# fpv2.net
KiCad netlist of a schematic drawn in EAGLE
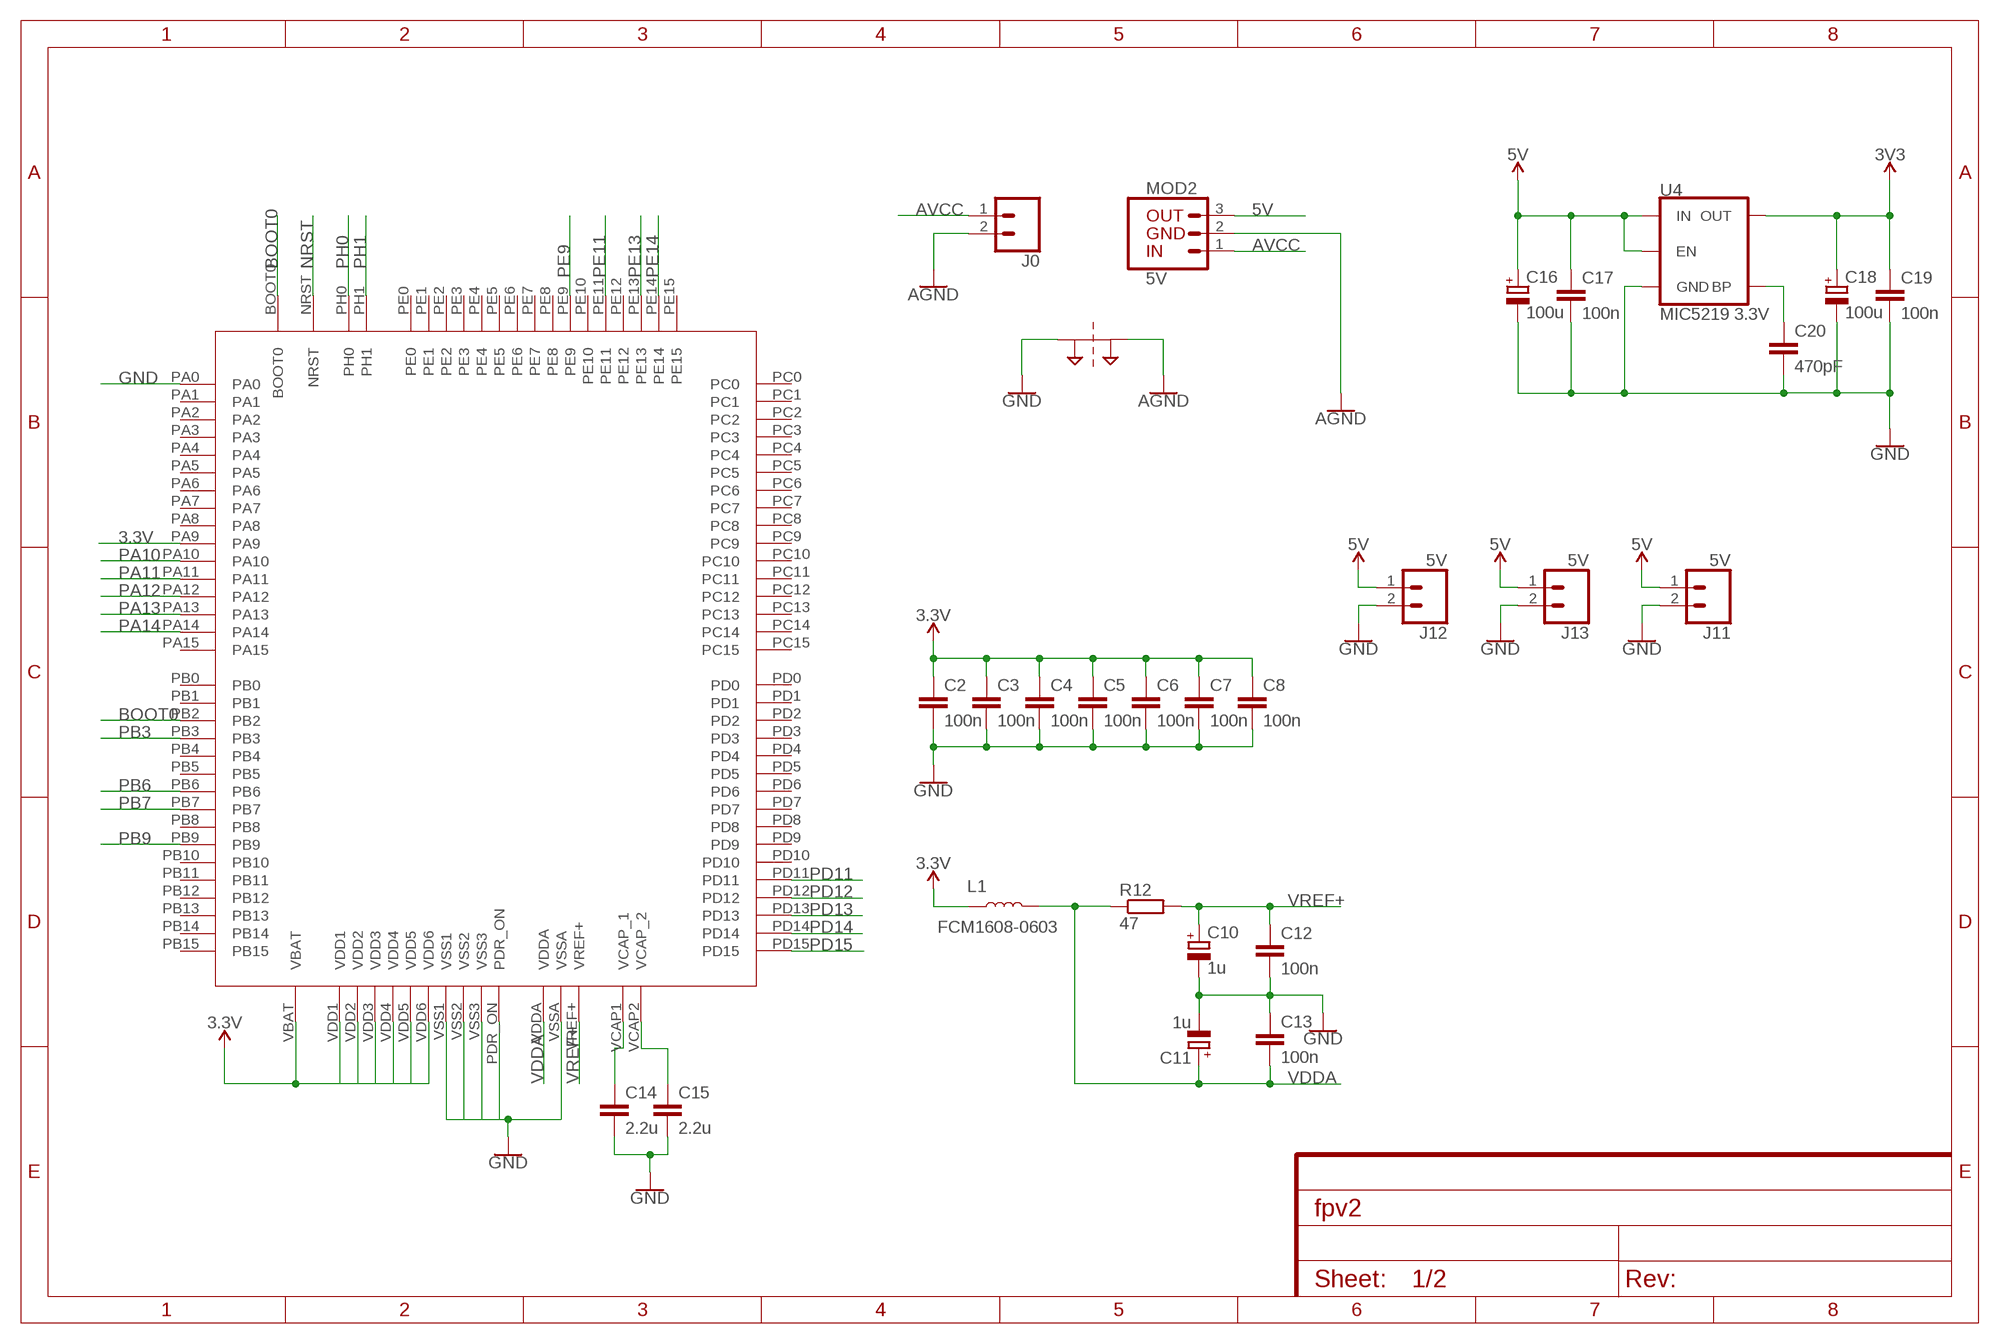
[diagram p0: schematic, sheet 1]
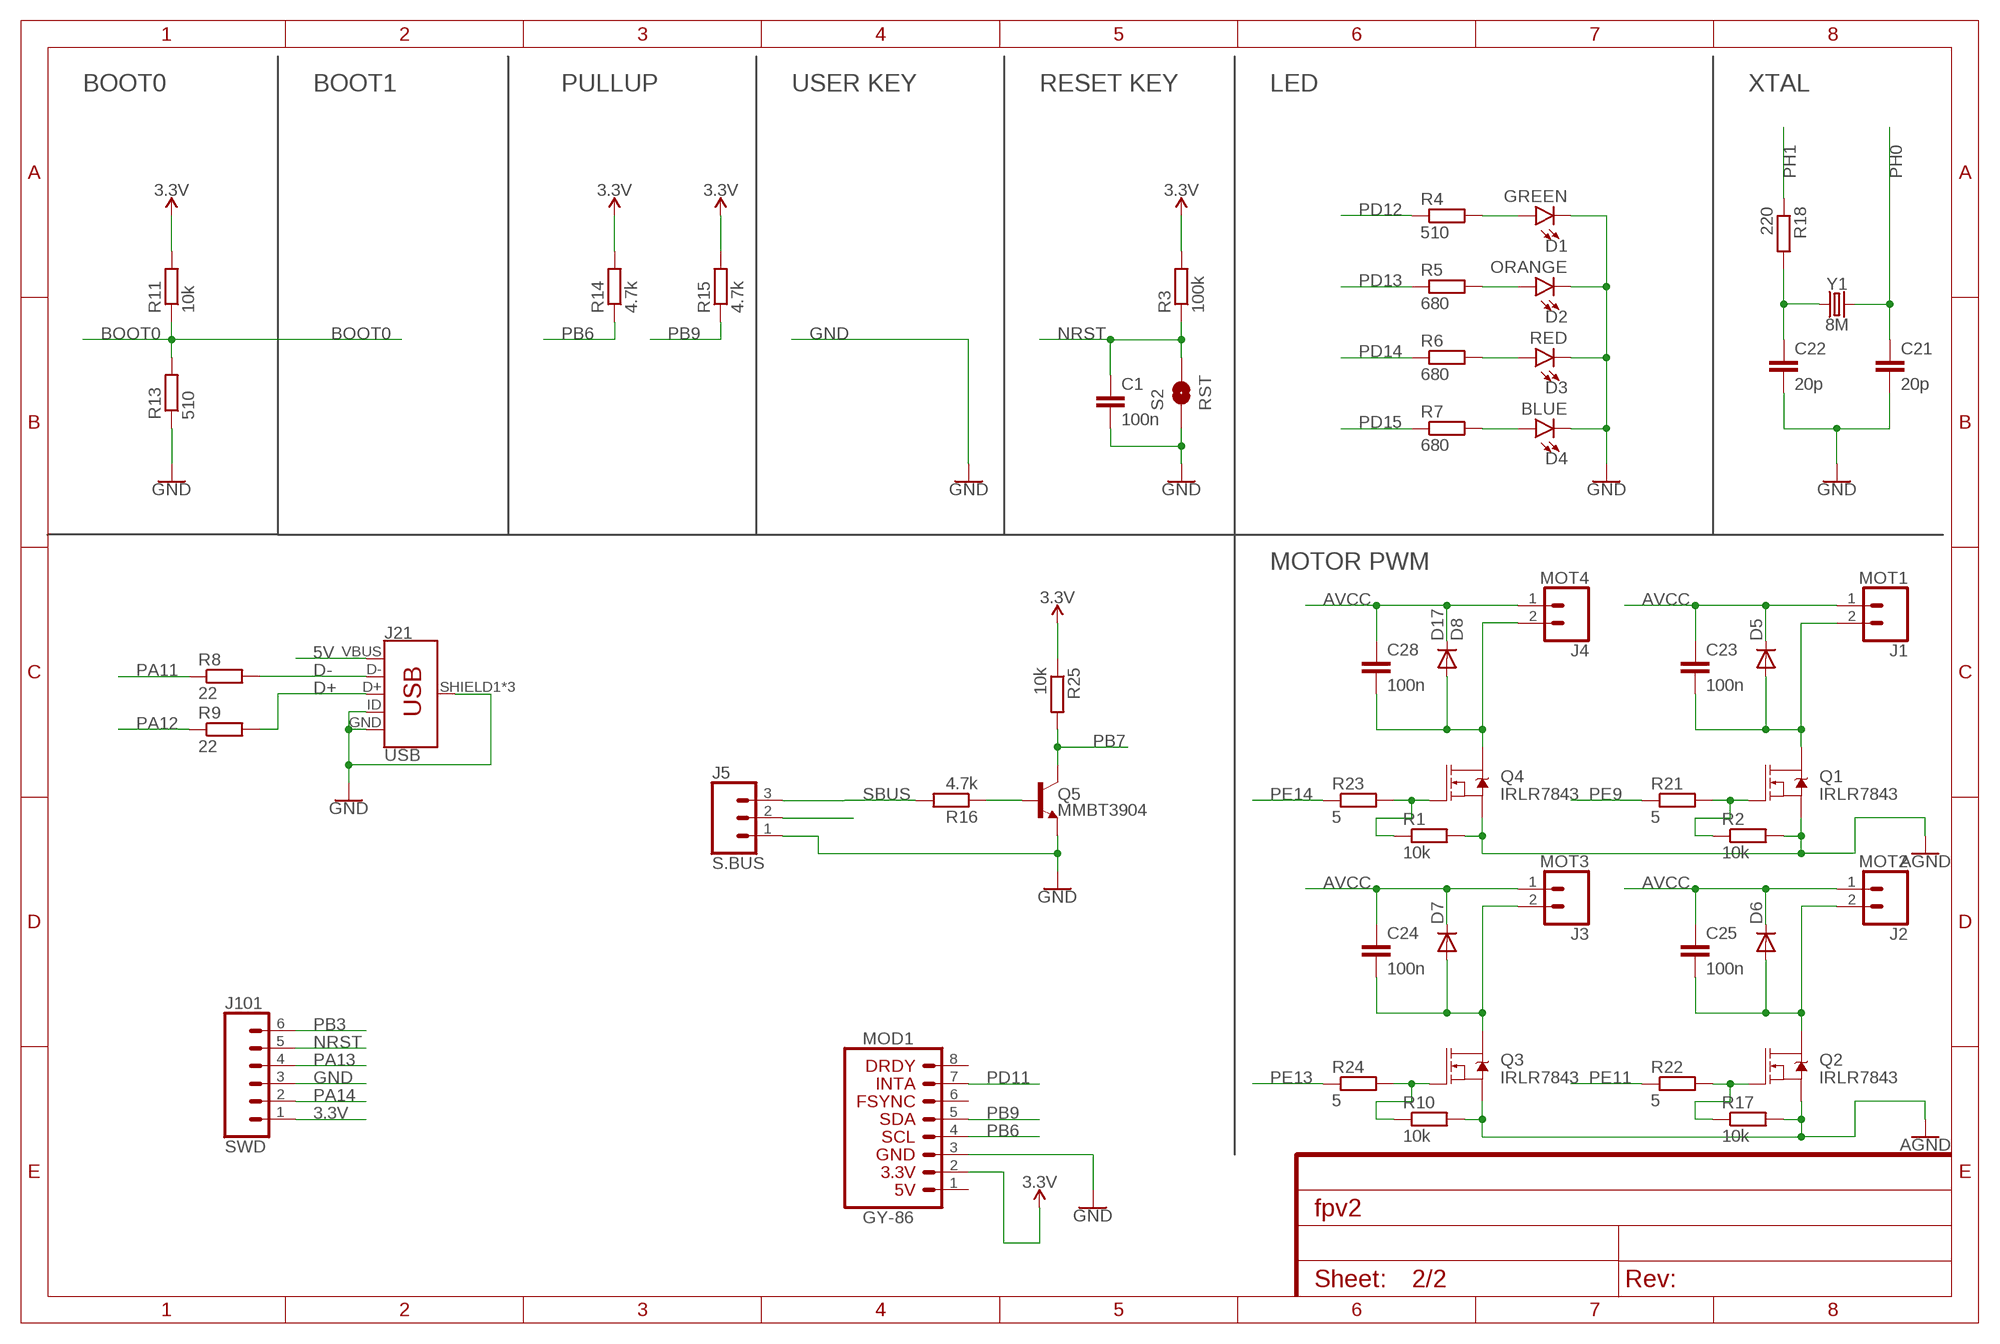
[diagram p1: schematic, sheet 2]

(export (version "E")
  (design (tool "Eeschema 10.0.6"))
  (components
    (comp (ref "C2")
      (value "100n")
      (footprint "eagle-import:C0603")
      (libsource (lib "eagle-import") (part "C-EUC0603"))
    )
    (comp (ref "C3")
      (value "100n")
      (footprint "eagle-import:C0603")
      (libsource (lib "eagle-import") (part "C-EUC0603"))
    )
    (comp (ref "C4")
      (value "100n")
      (footprint "eagle-import:C0603")
      (libsource (lib "eagle-import") (part "C-EUC0603"))
    )
    (comp (ref "C5")
      (value "100n")
      (footprint "eagle-import:C0603")
      (libsource (lib "eagle-import") (part "C-EUC0603"))
    )
    (comp (ref "C6")
      (value "100n")
      (footprint "eagle-import:C0603")
      (libsource (lib "eagle-import") (part "C-EUC0603"))
    )
    (comp (ref "C7")
      (value "100n")
      (footprint "eagle-import:C0603")
      (libsource (lib "eagle-import") (part "C-EUC0603"))
    )
    (comp (ref "C8")
      (value "100n")
      (footprint "eagle-import:C0603")
      (libsource (lib "eagle-import") (part "C-EUC0603"))
    )
    (comp (ref "C10")
      (value "1u")
      (footprint "eagle-import:A_3216-18R")
      (libsource (lib "eagle-import") (part "CPOL-EUA/3216-18R"))
    )
    (comp (ref "C11")
      (value "1u")
      (footprint "eagle-import:A_3216-18R")
      (libsource (lib "eagle-import") (part "CPOL-EUA/3216-18R"))
    )
    (comp (ref "C12")
      (value "100n")
      (footprint "eagle-import:C0603")
      (libsource (lib "eagle-import") (part "C-EUC0603"))
    )
    (comp (ref "C13")
      (value "100n")
      (footprint "eagle-import:C0603")
      (libsource (lib "eagle-import") (part "C-EUC0603"))
    )
    (comp (ref "C14")
      (value "2.2u")
      (footprint "eagle-import:C1206")
      (libsource (lib "eagle-import") (part "C-EUC1206"))
    )
    (comp (ref "C15")
      (value "2.2u")
      (footprint "eagle-import:C1206")
      (libsource (lib "eagle-import") (part "C-EUC1206"))
    )
    (comp (ref "C16")
      (value "100u")
      (footprint "eagle-import:SMC_B")
      (libsource (lib "eagle-import") (part "CPOL-EUSMCB"))
    )
    (comp (ref "C17")
      (value "100n")
      (footprint "eagle-import:C0603")
      (libsource (lib "eagle-import") (part "C-EUC0603"))
    )
    (comp (ref "C18")
      (value "100u")
      (footprint "eagle-import:SMC_B")
      (libsource (lib "eagle-import") (part "CPOL-EUSMCB"))
    )
    (comp (ref "C19")
      (value "100n")
      (footprint "eagle-import:C0603")
      (libsource (lib "eagle-import") (part "C-EUC0603"))
    )
    (comp (ref "C20")
      (value "470pF")
      (footprint "eagle-import:C0603")
      (libsource (lib "eagle-import") (part "C-EUC0603"))
    )
    (comp (ref "J0")
      (value "CONN_02LOCK_LONGPADS")
      (footprint "eagle-import:1X02_LOCK_LONGPADS")
      (libsource (lib "eagle-import") (part "CONN_02LOCK_LONGPADS"))
    )
    (comp (ref "J11")
      (value "5V")
      (footprint "eagle-import:SMD")
      (libsource (lib "eagle-import") (part "CONN-02SMD"))
    )
    (comp (ref "J12")
      (value "5V")
      (footprint "eagle-import:SMD")
      (libsource (lib "eagle-import") (part "CONN-02SMD"))
    )
    (comp (ref "J13")
      (value "5V")
      (footprint "eagle-import:SMD")
      (libsource (lib "eagle-import") (part "CONN-02SMD"))
    )
    (comp (ref "L1")
      (value "FCM1608-0603")
      (footprint "eagle-import:0603")
      (libsource (lib "eagle-import") (part "INDUCTOR-0603-33NH"))
    )
    (comp (ref "MOD2")
      (value "5V")
      (footprint "eagle-import:1X03")
      (libsource (lib "eagle-import") (part "TPS-MODULE"))
    )
    (comp (ref "R12")
      (value "47")
      (footprint "eagle-import:R0603")
      (libsource (lib "eagle-import") (part "R-EU_R0603"))
    )
    (comp (ref "SUPPLY1")
      (value "2PT_GND_TIE")
      (footprint "eagle-import:2PT_GND_TIE")
      (libsource (lib "eagle-import") (part "2PT_GND_TIE"))
    )
    (comp (ref "U1")
      (value "STM32F407VGT6")
      (footprint "eagle-import:LQFP100")
      (libsource (lib "eagle-import") (part "STM32F4V_100PIN_GENERIC"))
    )
    (comp (ref "U4")
      (value "MIC5219 3.3V")
      (footprint "eagle-import:SOT23-5")
      (libsource (lib "eagle-import") (part "V_REG_MIC52193.3V"))
    )
    (comp (ref "C1")
      (value "100n")
      (footprint "eagle-import:C0603")
      (libsource (lib "eagle-import") (part "C-EUC0603"))
    )
    (comp (ref "C21")
      (value "20p")
      (footprint "eagle-import:C0603")
      (libsource (lib "eagle-import") (part "C-EUC0603"))
    )
    (comp (ref "C22")
      (value "20p")
      (footprint "eagle-import:C0603")
      (libsource (lib "eagle-import") (part "C-EUC0603"))
    )
    (comp (ref "C23")
      (value "100n")
      (footprint "eagle-import:C0603")
      (libsource (lib "eagle-import") (part "C-EUC0603"))
    )
    (comp (ref "C24")
      (value "100n")
      (footprint "eagle-import:C0603")
      (libsource (lib "eagle-import") (part "C-EUC0603"))
    )
    (comp (ref "C25")
      (value "100n")
      (footprint "eagle-import:C0603")
      (libsource (lib "eagle-import") (part "C-EUC0603"))
    )
    (comp (ref "C28")
      (value "100n")
      (footprint "eagle-import:C0603")
      (libsource (lib "eagle-import") (part "C-EUC0603"))
    )
    (comp (ref "D1")
      (value "GREEN")
      (footprint "eagle-import:LED-0603")
      (libsource (lib "eagle-import") (part "LED0603"))
    )
    (comp (ref "D2")
      (value "ORANGE")
      (footprint "eagle-import:LED-0603")
      (libsource (lib "eagle-import") (part "LED0603"))
    )
    (comp (ref "D3")
      (value "RED")
      (footprint "eagle-import:LED-0603")
      (libsource (lib "eagle-import") (part "LED0603"))
    )
    (comp (ref "D4")
      (value "BLUE")
      (footprint "eagle-import:LED-0603")
      (libsource (lib "eagle-import") (part "LED0603"))
    )
    (comp (ref "D5")
      (value "DIODE-DO214AC")
      (footprint "eagle-import:DO214AC")
      (libsource (lib "eagle-import") (part "DIODE-DO214AC"))
    )
    (comp (ref "D6")
      (value "DIODE-DO214AC")
      (footprint "eagle-import:DO214AC")
      (libsource (lib "eagle-import") (part "DIODE-DO214AC"))
    )
    (comp (ref "D7")
      (value "DIODE-DO214AC")
      (footprint "eagle-import:DO214AC")
      (libsource (lib "eagle-import") (part "DIODE-DO214AC"))
    )
    (comp (ref "D17")
      (value "D8")
      (footprint "eagle-import:DO214AC")
      (libsource (lib "eagle-import") (part "DIODE-DO214AC"))
    )
    (comp (ref "J1")
      (value "MOT1")
      (footprint "eagle-import:1X02_LOCK_LONGPADS")
      (libsource (lib "eagle-import") (part "CONN_02LOCK_LONGPADS"))
    )
    (comp (ref "J2")
      (value "MOT2")
      (footprint "eagle-import:1X02_LOCK_LONGPADS")
      (libsource (lib "eagle-import") (part "CONN_02LOCK_LONGPADS"))
    )
    (comp (ref "J3")
      (value "MOT3")
      (footprint "eagle-import:1X02_LOCK_LONGPADS")
      (libsource (lib "eagle-import") (part "CONN_02LOCK_LONGPADS"))
    )
    (comp (ref "J4")
      (value "MOT4")
      (footprint "eagle-import:1X02_LOCK_LONGPADS")
      (libsource (lib "eagle-import") (part "CONN_02LOCK_LONGPADS"))
    )
    (comp (ref "J5")
      (value "S.BUS")
      (footprint "eagle-import:1X03")
      (libsource (lib "eagle-import") (part "CONN_03"))
    )
    (comp (ref "J21")
      (value "USB")
      (footprint "eagle-import:USB-B-MICRO-SMD")
      (libsource (lib "eagle-import") (part "USB_MICRO-B_FEMALE-SMT"))
    )
    (comp (ref "J101")
      (value "SWD")
      (footprint "eagle-import:1X06-SMD-FEMALE")
      (libsource (lib "eagle-import") (part "CONN_06SMD-FEMALE-V2"))
    )
    (comp (ref "MOD1")
      (value "GY-86")
      (footprint "eagle-import:GY-86")
      (libsource (lib "eagle-import") (part "GY-86"))
    )
    (comp (ref "Q1")
      (value "IRLR7843")
      (footprint "eagle-import:DPAK")
      (libsource (lib "eagle-import") (part "MOSFET-NCH-FDD8780"))
    )
    (comp (ref "Q2")
      (value "IRLR7843")
      (footprint "eagle-import:DPAK")
      (libsource (lib "eagle-import") (part "MOSFET-NCH-FDD8780"))
    )
    (comp (ref "Q3")
      (value "IRLR7843")
      (footprint "eagle-import:DPAK")
      (libsource (lib "eagle-import") (part "MOSFET-NCH-FDD8780"))
    )
    (comp (ref "Q4")
      (value "IRLR7843")
      (footprint "eagle-import:DPAK")
      (libsource (lib "eagle-import") (part "MOSFET-NCH-FDD8780"))
    )
    (comp (ref "Q5")
      (value "MMBT3904")
      (footprint "eagle-import:SOT23-3")
      (libsource (lib "eagle-import") (part "TRANS_NPN-MMBT2222AL"))
    )
    (comp (ref "R1")
      (value "10k")
      (footprint "eagle-import:R0603")
      (libsource (lib "eagle-import") (part "R-EU_R0603"))
    )
    (comp (ref "R2")
      (value "10k")
      (footprint "eagle-import:R0603")
      (libsource (lib "eagle-import") (part "R-EU_R0603"))
    )
    (comp (ref "R3")
      (value "100k")
      (footprint "eagle-import:R0603")
      (libsource (lib "eagle-import") (part "R-EU_R0603"))
    )
    (comp (ref "R4")
      (value "510")
      (footprint "eagle-import:R0603")
      (libsource (lib "eagle-import") (part "R-EU_R0603"))
    )
    (comp (ref "R5")
      (value "680")
      (footprint "eagle-import:R0603")
      (libsource (lib "eagle-import") (part "R-EU_R0603"))
    )
    (comp (ref "R6")
      (value "680")
      (footprint "eagle-import:R0603")
      (libsource (lib "eagle-import") (part "R-EU_R0603"))
    )
    (comp (ref "R7")
      (value "680")
      (footprint "eagle-import:R0603")
      (libsource (lib "eagle-import") (part "R-EU_R0603"))
    )
    (comp (ref "R8")
      (value "22")
      (footprint "eagle-import:R0603")
      (libsource (lib "eagle-import") (part "R-EU_R0603"))
    )
    (comp (ref "R9")
      (value "22")
      (footprint "eagle-import:R0603")
      (libsource (lib "eagle-import") (part "R-EU_R0603"))
    )
    (comp (ref "R10")
      (value "10k")
      (footprint "eagle-import:R0603")
      (libsource (lib "eagle-import") (part "R-EU_R0603"))
    )
    (comp (ref "R11")
      (value "10k")
      (footprint "eagle-import:R0603")
      (libsource (lib "eagle-import") (part "R-EU_R0603"))
    )
    (comp (ref "R13")
      (value "510")
      (footprint "eagle-import:R0603")
      (libsource (lib "eagle-import") (part "R-EU_R0603"))
    )
    (comp (ref "R14")
      (value "4.7k")
      (footprint "eagle-import:R0603")
      (libsource (lib "eagle-import") (part "R-EU_R0603"))
    )
    (comp (ref "R15")
      (value "4.7k")
      (footprint "eagle-import:R0603")
      (libsource (lib "eagle-import") (part "R-EU_R0603"))
    )
    (comp (ref "R16")
      (value "4.7k")
      (footprint "eagle-import:R0603")
      (libsource (lib "eagle-import") (part "R-EU_R0603"))
    )
    (comp (ref "R17")
      (value "10k")
      (footprint "eagle-import:R0603")
      (libsource (lib "eagle-import") (part "R-EU_R0603"))
    )
    (comp (ref "R18")
      (value "220")
      (footprint "eagle-import:R0603")
      (libsource (lib "eagle-import") (part "R-EU_R0603"))
    )
    (comp (ref "R21")
      (value "5")
      (footprint "eagle-import:R0603")
      (libsource (lib "eagle-import") (part "R-EU_R0603"))
    )
    (comp (ref "R22")
      (value "5")
      (footprint "eagle-import:R0603")
      (libsource (lib "eagle-import") (part "R-EU_R0603"))
    )
    (comp (ref "R23")
      (value "5")
      (footprint "eagle-import:R0603")
      (libsource (lib "eagle-import") (part "R-EU_R0603"))
    )
    (comp (ref "R24")
      (value "5")
      (footprint "eagle-import:R0603")
      (libsource (lib "eagle-import") (part "R-EU_R0603"))
    )
    (comp (ref "R25")
      (value "10k")
      (footprint "eagle-import:R0603")
      (libsource (lib "eagle-import") (part "R-EU_R0603"))
    )
    (comp (ref "S2")
      (value "RST")
      (footprint "eagle-import:SMT-JUMPER_2_NO_NO-SILK")
      (libsource (lib "eagle-import") (part "JUMPER-SMT_2_NO_NO-SILK"))
    )
    (comp (ref "Y1")
      (value "8M")
      (footprint "eagle-import:CRYSTAL-SMD-5X3.2-2PAD")
      (libsource (lib "eagle-import") (part "CRYSTALSMD-5X3.2-2PAD"))
    )
  )
  (nets
    (net (code "1") (name "3.3V") (class "Default")
      (node (ref "C18") (pin "+") (pinfunction "+_+") (pintype "passive"))
      (node (ref "C19") (pin "1") (pinfunction "1_1") (pintype "passive"))
      (node (ref "C2") (pin "1") (pinfunction "1_1") (pintype "passive"))
      (node (ref "C3") (pin "1") (pinfunction "1_1") (pintype "passive"))
      (node (ref "C4") (pin "1") (pinfunction "1_1") (pintype "passive"))
      (node (ref "C5") (pin "1") (pinfunction "1_1") (pintype "passive"))
      (node (ref "C6") (pin "1") (pinfunction "1_1") (pintype "passive"))
      (node (ref "C7") (pin "1") (pinfunction "1_1") (pintype "passive"))
      (node (ref "C8") (pin "1") (pinfunction "1_1") (pintype "passive"))
      (node (ref "J101") (pin "1") (pinfunction "1_1") (pintype "passive"))
      (node (ref "L1") (pin "1") (pinfunction "1_1") (pintype "passive"))
      (node (ref "MOD1") (pin "2") (pinfunction "3.3V_2") (pintype "passive"))
      (node (ref "R11") (pin "2") (pinfunction "2_2") (pintype "passive"))
      (node (ref "R14") (pin "2") (pinfunction "2_2") (pintype "passive"))
      (node (ref "R15") (pin "2") (pinfunction "2_2") (pintype "passive"))
      (node (ref "R25") (pin "1") (pinfunction "1_1") (pintype "passive"))
      (node (ref "R3") (pin "2") (pinfunction "2_2") (pintype "passive"))
      (node (ref "U1") (pin "PA9") (pinfunction "PA9_PA9") (pintype "bidirectional"))
      (node (ref "U1") (pin "VBAT") (pinfunction "VBAT_VBAT") (pintype "bidirectional"))
      (node (ref "U1") (pin "VDD1") (pinfunction "VDD1_VDD1") (pintype "bidirectional"))
      (node (ref "U1") (pin "VDD2") (pinfunction "VDD2_VDD2") (pintype "bidirectional"))
      (node (ref "U1") (pin "VDD3") (pinfunction "VDD3_VDD3") (pintype "bidirectional"))
      (node (ref "U1") (pin "VDD4") (pinfunction "VDD4_VDD4") (pintype "bidirectional"))
      (node (ref "U1") (pin "VDD5") (pinfunction "VDD5_VDD5") (pintype "bidirectional"))
      (node (ref "U1") (pin "VDD6") (pinfunction "VDD6_VDD6") (pintype "bidirectional"))
      (node (ref "U4") (pin "5") (pinfunction "OUT_5") (pintype "passive"))
    )
    (net (code "2") (name "5V") (class "Default")
      (node (ref "C16") (pin "+") (pinfunction "+_+") (pintype "passive"))
      (node (ref "C17") (pin "1") (pinfunction "1_1") (pintype "passive"))
      (node (ref "J11") (pin "1") (pinfunction "1_1") (pintype "passive"))
      (node (ref "J12") (pin "1") (pinfunction "1_1") (pintype "passive"))
      (node (ref "J13") (pin "1") (pinfunction "1_1") (pintype "passive"))
      (node (ref "J21") (pin "VBUS") (pinfunction "VBUS_VBUS") (pintype "power_in"))
      (node (ref "J5") (pin "2") (pinfunction "2_2") (pintype "passive"))
      (node (ref "MOD2") (pin "3") (pinfunction "3_3") (pintype "passive"))
      (node (ref "U4") (pin "1") (pinfunction "IN_1") (pintype "input"))
      (node (ref "U4") (pin "3") (pinfunction "EN_3") (pintype "input"))
    )
    (net (code "3") (name "AGND") (class "Default")
      (node (ref "J0") (pin "2") (pinfunction "2_2") (pintype "passive"))
      (node (ref "MOD2") (pin "2") (pinfunction "2_2") (pintype "passive"))
      (node (ref "Q1") (pin "3") (pinfunction "S_3") (pintype "bidirectional"))
      (node (ref "Q2") (pin "3") (pinfunction "S_3") (pintype "bidirectional"))
      (node (ref "Q3") (pin "3") (pinfunction "S_3") (pintype "bidirectional"))
      (node (ref "Q4") (pin "3") (pinfunction "S_3") (pintype "bidirectional"))
      (node (ref "R1") (pin "2") (pinfunction "2_2") (pintype "passive"))
      (node (ref "R10") (pin "2") (pinfunction "2_2") (pintype "passive"))
      (node (ref "R17") (pin "2") (pinfunction "2_2") (pintype "passive"))
      (node (ref "R2") (pin "2") (pinfunction "2_2") (pintype "passive"))
      (node (ref "SUPPLY1") (pin "P$2") (pinfunction "P$2_P$2") (pintype "bidirectional"))
    )
    (net (code "4") (name "AVCC") (class "Default")
      (node (ref "C23") (pin "1") (pinfunction "1_1") (pintype "passive"))
      (node (ref "C24") (pin "1") (pinfunction "1_1") (pintype "passive"))
      (node (ref "C25") (pin "1") (pinfunction "1_1") (pintype "passive"))
      (node (ref "C28") (pin "1") (pinfunction "1_1") (pintype "passive"))
      (node (ref "D17") (pin "C") (pinfunction "C_C") (pintype "passive"))
      (node (ref "D5") (pin "C") (pinfunction "C_C") (pintype "passive"))
      (node (ref "D6") (pin "C") (pinfunction "C_C") (pintype "passive"))
      (node (ref "D7") (pin "C") (pinfunction "C_C") (pintype "passive"))
      (node (ref "J0") (pin "1") (pinfunction "1_1") (pintype "passive"))
      (node (ref "J1") (pin "1") (pinfunction "1_1") (pintype "passive"))
      (node (ref "J2") (pin "1") (pinfunction "1_1") (pintype "passive"))
      (node (ref "J3") (pin "1") (pinfunction "1_1") (pintype "passive"))
      (node (ref "J4") (pin "1") (pinfunction "1_1") (pintype "passive"))
      (node (ref "MOD2") (pin "1") (pinfunction "1_1") (pintype "passive"))
    )
    (net (code "5") (name "BOOT0") (class "Default")
      (node (ref "R11") (pin "1") (pinfunction "1_1") (pintype "passive"))
      (node (ref "R13") (pin "2") (pinfunction "2_2") (pintype "passive"))
      (node (ref "U1") (pin "BOOT0") (pinfunction "BOOT0_BOOT0") (pintype "bidirectional"))
      (node (ref "U1") (pin "PB2") (pinfunction "PB2_PB2") (pintype "bidirectional"))
    )
    (net (code "6") (name "D+") (class "Default")
      (node (ref "J21") (pin "D+") (pinfunction "D+_D+") (pintype "bidirectional"))
      (node (ref "R9") (pin "2") (pinfunction "2_2") (pintype "passive"))
    )
    (net (code "7") (name "D-") (class "Default")
      (node (ref "J21") (pin "D-") (pinfunction "D-_D-") (pintype "bidirectional"))
      (node (ref "R8") (pin "2") (pinfunction "2_2") (pintype "passive"))
    )
    (net (code "8") (name "GND") (class "Default")
      (node (ref "C1") (pin "2") (pinfunction "2_2") (pintype "passive"))
      (node (ref "C10") (pin "-") (pinfunction "-_-") (pintype "passive"))
      (node (ref "C11") (pin "-") (pinfunction "-_-") (pintype "passive"))
      (node (ref "C12") (pin "2") (pinfunction "2_2") (pintype "passive"))
      (node (ref "C13") (pin "1") (pinfunction "1_1") (pintype "passive"))
      (node (ref "C14") (pin "2") (pinfunction "2_2") (pintype "passive"))
      (node (ref "C15") (pin "2") (pinfunction "2_2") (pintype "passive"))
      (node (ref "C16") (pin "-") (pinfunction "-_-") (pintype "passive"))
      (node (ref "C17") (pin "2") (pinfunction "2_2") (pintype "passive"))
      (node (ref "C18") (pin "-") (pinfunction "-_-") (pintype "passive"))
      (node (ref "C19") (pin "2") (pinfunction "2_2") (pintype "passive"))
      (node (ref "C2") (pin "2") (pinfunction "2_2") (pintype "passive"))
      (node (ref "C20") (pin "2") (pinfunction "2_2") (pintype "passive"))
      (node (ref "C21") (pin "2") (pinfunction "2_2") (pintype "passive"))
      (node (ref "C22") (pin "2") (pinfunction "2_2") (pintype "passive"))
      (node (ref "C3") (pin "2") (pinfunction "2_2") (pintype "passive"))
      (node (ref "C4") (pin "2") (pinfunction "2_2") (pintype "passive"))
      (node (ref "C5") (pin "2") (pinfunction "2_2") (pintype "passive"))
      (node (ref "C6") (pin "2") (pinfunction "2_2") (pintype "passive"))
      (node (ref "C7") (pin "2") (pinfunction "2_2") (pintype "passive"))
      (node (ref "C8") (pin "2") (pinfunction "2_2") (pintype "passive"))
      (node (ref "D1") (pin "C") (pinfunction "C_C") (pintype "passive"))
      (node (ref "D2") (pin "C") (pinfunction "C_C") (pintype "passive"))
      (node (ref "D3") (pin "C") (pinfunction "C_C") (pintype "passive"))
      (node (ref "D4") (pin "C") (pinfunction "C_C") (pintype "passive"))
      (node (ref "J101") (pin "3") (pinfunction "3_3") (pintype "passive"))
      (node (ref "J11") (pin "2") (pinfunction "2_2") (pintype "passive"))
      (node (ref "J12") (pin "2") (pinfunction "2_2") (pintype "passive"))
      (node (ref "J13") (pin "2") (pinfunction "2_2") (pintype "passive"))
      (node (ref "J21") (pin "GND") (pinfunction "GND_GND") (pintype "power_in"))
      (node (ref "J21") (pin "ID") (pinfunction "ID_ID") (pintype "bidirectional"))
      (node (ref "J21") (pin "SHIELD1") (pinfunction "SHIELD_SHIELD1") (pintype "bidirectional"))
      (node (ref "J21") (pin "SHIELD2") (pinfunction "SHIELD_SHIELD2") (pintype "bidirectional"))
      (node (ref "J21") (pin "SHIELD3") (pinfunction "SHIELD_SHIELD3") (pintype "bidirectional"))
      (node (ref "J5") (pin "1") (pinfunction "1_1") (pintype "passive"))
      (node (ref "MOD1") (pin "3") (pinfunction "GND_3") (pintype "passive"))
      (node (ref "Q5") (pin "2") (pinfunction "E_2") (pintype "passive"))
      (node (ref "R13") (pin "1") (pinfunction "1_1") (pintype "passive"))
      (node (ref "S2") (pin "1") (pinfunction "1_1") (pintype "passive"))
      (node (ref "SUPPLY1") (pin "P$1") (pinfunction "P$1_P$1") (pintype "bidirectional"))
      (node (ref "U1") (pin "PA0") (pinfunction "PA0_PA0") (pintype "bidirectional"))
      (node (ref "U1") (pin "PDR_ON") (pinfunction "PDR_ON_PDR_ON") (pintype "bidirectional"))
      (node (ref "U1") (pin "VSS1") (pinfunction "VSS1_VSS1") (pintype "bidirectional"))
      (node (ref "U1") (pin "VSS2") (pinfunction "VSS2_VSS2") (pintype "bidirectional"))
      (node (ref "U1") (pin "VSS3") (pinfunction "VSS3_VSS3") (pintype "bidirectional"))
      (node (ref "U1") (pin "VSSA") (pinfunction "VSSA_VSSA") (pintype "bidirectional"))
      (node (ref "U4") (pin "2") (pinfunction "GND_2") (pintype "input"))
    )
    (net (code "9") (name "NRST") (class "Default")
      (node (ref "C1") (pin "1") (pinfunction "1_1") (pintype "passive"))
      (node (ref "J101") (pin "5") (pinfunction "5_5") (pintype "passive"))
      (node (ref "R3") (pin "1") (pinfunction "1_1") (pintype "passive"))
      (node (ref "S2") (pin "2") (pinfunction "2_2") (pintype "passive"))
      (node (ref "U1") (pin "NRST") (pinfunction "NRST_NRST") (pintype "bidirectional"))
    )
    (net (code "10") (name "Net-(D1-PadA)") (class "Default")
      (node (ref "D1") (pin "A") (pinfunction "A_A") (pintype "passive"))
      (node (ref "R4") (pin "2") (pinfunction "2_2") (pintype "passive"))
    )
    (net (code "11") (name "Net-(D2-PadA)") (class "Default")
      (node (ref "D2") (pin "A") (pinfunction "A_A") (pintype "passive"))
      (node (ref "R5") (pin "2") (pinfunction "2_2") (pintype "passive"))
    )
    (net (code "12") (name "Net-(D3-PadA)") (class "Default")
      (node (ref "D3") (pin "A") (pinfunction "A_A") (pintype "passive"))
      (node (ref "R6") (pin "2") (pinfunction "2_2") (pintype "passive"))
    )
    (net (code "13") (name "Net-(D4-PadA)") (class "Default")
      (node (ref "D4") (pin "A") (pinfunction "A_A") (pintype "passive"))
      (node (ref "R7") (pin "2") (pinfunction "2_2") (pintype "passive"))
    )
    (net (code "14") (name "Net-(Q1-D)") (class "Default")
      (node (ref "C23") (pin "2") (pinfunction "2_2") (pintype "passive"))
      (node (ref "D5") (pin "A") (pinfunction "A_A") (pintype "passive"))
      (node (ref "J1") (pin "2") (pinfunction "2_2") (pintype "passive"))
      (node (ref "Q1") (pin "4") (pinfunction "D_4") (pintype "bidirectional"))
    )
    (net (code "15") (name "Net-(Q1-G)") (class "Default")
      (node (ref "Q1") (pin "1") (pinfunction "G_1") (pintype "bidirectional"))
      (node (ref "R2") (pin "1") (pinfunction "1_1") (pintype "passive"))
      (node (ref "R21") (pin "2") (pinfunction "2_2") (pintype "passive"))
    )
    (net (code "16") (name "Net-(Q2-D)") (class "Default")
      (node (ref "C25") (pin "2") (pinfunction "2_2") (pintype "passive"))
      (node (ref "D6") (pin "A") (pinfunction "A_A") (pintype "passive"))
      (node (ref "J2") (pin "2") (pinfunction "2_2") (pintype "passive"))
      (node (ref "Q2") (pin "4") (pinfunction "D_4") (pintype "bidirectional"))
    )
    (net (code "17") (name "Net-(Q2-G)") (class "Default")
      (node (ref "Q2") (pin "1") (pinfunction "G_1") (pintype "bidirectional"))
      (node (ref "R17") (pin "1") (pinfunction "1_1") (pintype "passive"))
      (node (ref "R22") (pin "2") (pinfunction "2_2") (pintype "passive"))
    )
    (net (code "18") (name "Net-(Q3-D)") (class "Default")
      (node (ref "C24") (pin "2") (pinfunction "2_2") (pintype "passive"))
      (node (ref "D7") (pin "A") (pinfunction "A_A") (pintype "passive"))
      (node (ref "J3") (pin "2") (pinfunction "2_2") (pintype "passive"))
      (node (ref "Q3") (pin "4") (pinfunction "D_4") (pintype "bidirectional"))
    )
    (net (code "19") (name "Net-(Q3-G)") (class "Default")
      (node (ref "Q3") (pin "1") (pinfunction "G_1") (pintype "bidirectional"))
      (node (ref "R10") (pin "1") (pinfunction "1_1") (pintype "passive"))
      (node (ref "R24") (pin "2") (pinfunction "2_2") (pintype "passive"))
    )
    (net (code "20") (name "Net-(Q4-D)") (class "Default")
      (node (ref "C28") (pin "2") (pinfunction "2_2") (pintype "passive"))
      (node (ref "D17") (pin "A") (pinfunction "A_A") (pintype "passive"))
      (node (ref "J4") (pin "2") (pinfunction "2_2") (pintype "passive"))
      (node (ref "Q4") (pin "4") (pinfunction "D_4") (pintype "bidirectional"))
    )
    (net (code "21") (name "Net-(Q4-G)") (class "Default")
      (node (ref "Q4") (pin "1") (pinfunction "G_1") (pintype "bidirectional"))
      (node (ref "R1") (pin "1") (pinfunction "1_1") (pintype "passive"))
      (node (ref "R23") (pin "2") (pinfunction "2_2") (pintype "passive"))
    )
    (net (code "22") (name "Net-(Q5-B)") (class "Default")
      (node (ref "Q5") (pin "1") (pinfunction "B_1") (pintype "passive"))
      (node (ref "R16") (pin "1") (pinfunction "1_1") (pintype "passive"))
    )
    (net (code "23") (name "Net-(U1-VCAP_1)") (class "Default")
      (node (ref "C14") (pin "1") (pinfunction "1_1") (pintype "passive"))
      (node (ref "U1") (pin "VCAP1") (pinfunction "VCAP_1_VCAP1") (pintype "bidirectional"))
    )
    (net (code "24") (name "Net-(U1-VCAP_2)") (class "Default")
      (node (ref "C15") (pin "1") (pinfunction "1_1") (pintype "passive"))
      (node (ref "U1") (pin "VCAP2") (pinfunction "VCAP_2_VCAP2") (pintype "bidirectional"))
    )
    (net (code "25") (name "Net-(U4-BP)") (class "Default")
      (node (ref "C20") (pin "1") (pinfunction "1_1") (pintype "passive"))
      (node (ref "U4") (pin "4") (pinfunction "BP_4") (pintype "input"))
    )
    (net (code "26") (name "Net-(Y1-1)") (class "Default")
      (node (ref "C22") (pin "1") (pinfunction "1_1") (pintype "passive"))
      (node (ref "R18") (pin "2") (pinfunction "2_2") (pintype "passive"))
      (node (ref "Y1") (pin "P$1") (pinfunction "1_P$1") (pintype "passive"))
    )
    (net (code "27") (name "PA10") (class "Default")
      (node (ref "U1") (pin "PA10") (pinfunction "PA10_PA10") (pintype "bidirectional"))
    )
    (net (code "28") (name "PA11") (class "Default")
      (node (ref "R8") (pin "1") (pinfunction "1_1") (pintype "passive"))
      (node (ref "U1") (pin "PA11") (pinfunction "PA11_PA11") (pintype "bidirectional"))
    )
    (net (code "29") (name "PA12") (class "Default")
      (node (ref "R9") (pin "1") (pinfunction "1_1") (pintype "passive"))
      (node (ref "U1") (pin "PA12") (pinfunction "PA12_PA12") (pintype "bidirectional"))
    )
    (net (code "30") (name "PA13") (class "Default")
      (node (ref "J101") (pin "4") (pinfunction "4_4") (pintype "passive"))
      (node (ref "U1") (pin "PA13") (pinfunction "PA13_PA13") (pintype "bidirectional"))
    )
    (net (code "31") (name "PA14") (class "Default")
      (node (ref "J101") (pin "2") (pinfunction "2_2") (pintype "passive"))
      (node (ref "U1") (pin "PA14") (pinfunction "PA14_PA14") (pintype "bidirectional"))
    )
    (net (code "32") (name "PB3") (class "Default")
      (node (ref "J101") (pin "6") (pinfunction "6_6") (pintype "passive"))
      (node (ref "U1") (pin "PB3") (pinfunction "PB3_PB3") (pintype "bidirectional"))
    )
    (net (code "33") (name "PB6") (class "Default")
      (node (ref "MOD1") (pin "4") (pinfunction "SCL_4") (pintype "passive"))
      (node (ref "R14") (pin "1") (pinfunction "1_1") (pintype "passive"))
      (node (ref "U1") (pin "PB6") (pinfunction "PB6_PB6") (pintype "bidirectional"))
    )
    (net (code "34") (name "PB7") (class "Default")
      (node (ref "Q5") (pin "3") (pinfunction "C_3") (pintype "passive"))
      (node (ref "R25") (pin "2") (pinfunction "2_2") (pintype "passive"))
      (node (ref "U1") (pin "PB7") (pinfunction "PB7_PB7") (pintype "bidirectional"))
    )
    (net (code "35") (name "PB9") (class "Default")
      (node (ref "MOD1") (pin "5") (pinfunction "SDA_5") (pintype "passive"))
      (node (ref "R15") (pin "1") (pinfunction "1_1") (pintype "passive"))
      (node (ref "U1") (pin "PB9") (pinfunction "PB9_PB9") (pintype "bidirectional"))
    )
    (net (code "36") (name "PD11") (class "Default")
      (node (ref "MOD1") (pin "7") (pinfunction "INTA_7") (pintype "passive"))
      (node (ref "U1") (pin "PD11") (pinfunction "PD11_PD11") (pintype "bidirectional"))
    )
    (net (code "37") (name "PD12") (class "Default")
      (node (ref "R4") (pin "1") (pinfunction "1_1") (pintype "passive"))
      (node (ref "U1") (pin "PD12") (pinfunction "PD12_PD12") (pintype "bidirectional"))
    )
    (net (code "38") (name "PD13") (class "Default")
      (node (ref "R5") (pin "1") (pinfunction "1_1") (pintype "passive"))
      (node (ref "U1") (pin "PD13") (pinfunction "PD13_PD13") (pintype "bidirectional"))
    )
    (net (code "39") (name "PD14") (class "Default")
      (node (ref "R6") (pin "1") (pinfunction "1_1") (pintype "passive"))
      (node (ref "U1") (pin "PD14") (pinfunction "PD14_PD14") (pintype "bidirectional"))
    )
    (net (code "40") (name "PD15") (class "Default")
      (node (ref "R7") (pin "1") (pinfunction "1_1") (pintype "passive"))
      (node (ref "U1") (pin "PD15") (pinfunction "PD15_PD15") (pintype "bidirectional"))
    )
    (net (code "41") (name "PE9") (class "Default")
      (node (ref "R21") (pin "1") (pinfunction "1_1") (pintype "passive"))
      (node (ref "U1") (pin "PE9") (pinfunction "PE9_PE9") (pintype "bidirectional"))
    )
    (net (code "42") (name "PE11") (class "Default")
      (node (ref "R22") (pin "1") (pinfunction "1_1") (pintype "passive"))
      (node (ref "U1") (pin "PE11") (pinfunction "PE11_PE11") (pintype "bidirectional"))
    )
    (net (code "43") (name "PE13") (class "Default")
      (node (ref "R24") (pin "1") (pinfunction "1_1") (pintype "passive"))
      (node (ref "U1") (pin "PE13") (pinfunction "PE13_PE13") (pintype "bidirectional"))
    )
    (net (code "44") (name "PE14") (class "Default")
      (node (ref "R23") (pin "1") (pinfunction "1_1") (pintype "passive"))
      (node (ref "U1") (pin "PE14") (pinfunction "PE14_PE14") (pintype "bidirectional"))
    )
    (net (code "45") (name "PH0") (class "Default")
      (node (ref "C21") (pin "1") (pinfunction "1_1") (pintype "passive"))
      (node (ref "U1") (pin "PH0") (pinfunction "PH0_PH0") (pintype "bidirectional"))
      (node (ref "Y1") (pin "P$2") (pinfunction "2_P$2") (pintype "passive"))
    )
    (net (code "46") (name "PH1") (class "Default")
      (node (ref "R18") (pin "1") (pinfunction "1_1") (pintype "passive"))
      (node (ref "U1") (pin "PH1") (pinfunction "PH1_PH1") (pintype "bidirectional"))
    )
    (net (code "47") (name "SBUS") (class "Default")
      (node (ref "J5") (pin "3") (pinfunction "3_3") (pintype "passive"))
      (node (ref "R16") (pin "2") (pinfunction "2_2") (pintype "passive"))
    )
    (net (code "48") (name "VDDA") (class "Default")
      (node (ref "C11") (pin "+") (pinfunction "+_+") (pintype "passive"))
      (node (ref "C13") (pin "2") (pinfunction "2_2") (pintype "passive"))
      (node (ref "L1") (pin "2") (pinfunction "2_2") (pintype "passive"))
      (node (ref "R12") (pin "1") (pinfunction "1_1") (pintype "passive"))
      (node (ref "U1") (pin "VDDA") (pinfunction "VDDA_VDDA") (pintype "bidirectional"))
    )
    (net (code "49") (name "VREF+") (class "Default")
      (node (ref "C10") (pin "+") (pinfunction "+_+") (pintype "passive"))
      (node (ref "C12") (pin "1") (pinfunction "1_1") (pintype "passive"))
      (node (ref "R12") (pin "2") (pinfunction "2_2") (pintype "passive"))
      (node (ref "U1") (pin "VREF+") (pinfunction "VREF+_VREF+") (pintype "bidirectional"))
    )
    (net (code "50") (name "unconnected-(MOD1-5V-Pad1)") (class "Default")
      (node (ref "MOD1") (pin "1") (pinfunction "5V_1") (pintype "passive"))
    )
    (net (code "51") (name "unconnected-(MOD1-DRDY-Pad8)") (class "Default")
      (node (ref "MOD1") (pin "8") (pinfunction "DRDY_8") (pintype "passive"))
    )
    (net (code "52") (name "unconnected-(MOD1-FSYNC-Pad6)") (class "Default")
      (node (ref "MOD1") (pin "6") (pinfunction "FSYNC_6") (pintype "passive"))
    )
    (net (code "53") (name "unconnected-(U1-PadPA1)") (class "Default")
      (node (ref "U1") (pin "PA1") (pinfunction "PA1_PA1") (pintype "bidirectional"))
    )
    (net (code "54") (name "unconnected-(U1-PadPA2)") (class "Default")
      (node (ref "U1") (pin "PA2") (pinfunction "PA2_PA2") (pintype "bidirectional"))
    )
    (net (code "55") (name "unconnected-(U1-PadPA3)") (class "Default")
      (node (ref "U1") (pin "PA3") (pinfunction "PA3_PA3") (pintype "bidirectional"))
    )
    (net (code "56") (name "unconnected-(U1-PadPA4)") (class "Default")
      (node (ref "U1") (pin "PA4") (pinfunction "PA4_PA4") (pintype "bidirectional"))
    )
    (net (code "57") (name "unconnected-(U1-PadPA5)") (class "Default")
      (node (ref "U1") (pin "PA5") (pinfunction "PA5_PA5") (pintype "bidirectional"))
    )
    (net (code "58") (name "unconnected-(U1-PadPA6)") (class "Default")
      (node (ref "U1") (pin "PA6") (pinfunction "PA6_PA6") (pintype "bidirectional"))
    )
    (net (code "59") (name "unconnected-(U1-PadPA7)") (class "Default")
      (node (ref "U1") (pin "PA7") (pinfunction "PA7_PA7") (pintype "bidirectional"))
    )
    (net (code "60") (name "unconnected-(U1-PadPA8)") (class "Default")
      (node (ref "U1") (pin "PA8") (pinfunction "PA8_PA8") (pintype "bidirectional"))
    )
    (net (code "61") (name "unconnected-(U1-PadPA15)") (class "Default")
      (node (ref "U1") (pin "PA15") (pinfunction "PA15_PA15") (pintype "bidirectional"))
    )
    (net (code "62") (name "unconnected-(U1-PadPB0)") (class "Default")
      (node (ref "U1") (pin "PB0") (pinfunction "PB0_PB0") (pintype "bidirectional"))
    )
    (net (code "63") (name "unconnected-(U1-PadPB1)") (class "Default")
      (node (ref "U1") (pin "PB1") (pinfunction "PB1_PB1") (pintype "bidirectional"))
    )
    (net (code "64") (name "unconnected-(U1-PadPB4)") (class "Default")
      (node (ref "U1") (pin "PB4") (pinfunction "PB4_PB4") (pintype "bidirectional"))
    )
    (net (code "65") (name "unconnected-(U1-PadPB5)") (class "Default")
      (node (ref "U1") (pin "PB5") (pinfunction "PB5_PB5") (pintype "bidirectional"))
    )
    (net (code "66") (name "unconnected-(U1-PadPB8)") (class "Default")
      (node (ref "U1") (pin "PB8") (pinfunction "PB8_PB8") (pintype "bidirectional"))
    )
    (net (code "67") (name "unconnected-(U1-PadPB10)") (class "Default")
      (node (ref "U1") (pin "PB10") (pinfunction "PB10_PB10") (pintype "bidirectional"))
    )
    (net (code "68") (name "unconnected-(U1-PadPB11)") (class "Default")
      (node (ref "U1") (pin "PB11") (pinfunction "PB11_PB11") (pintype "bidirectional"))
    )
    (net (code "69") (name "unconnected-(U1-PadPB12)") (class "Default")
      (node (ref "U1") (pin "PB12") (pinfunction "PB12_PB12") (pintype "bidirectional"))
    )
    (net (code "70") (name "unconnected-(U1-PadPB13)") (class "Default")
      (node (ref "U1") (pin "PB13") (pinfunction "PB13_PB13") (pintype "bidirectional"))
    )
    (net (code "71") (name "unconnected-(U1-PadPB14)") (class "Default")
      (node (ref "U1") (pin "PB14") (pinfunction "PB14_PB14") (pintype "bidirectional"))
    )
    (net (code "72") (name "unconnected-(U1-PadPB15)") (class "Default")
      (node (ref "U1") (pin "PB15") (pinfunction "PB15_PB15") (pintype "bidirectional"))
    )
    (net (code "73") (name "unconnected-(U1-PadPC0)") (class "Default")
      (node (ref "U1") (pin "PC0") (pinfunction "PC0_PC0") (pintype "bidirectional"))
    )
    (net (code "74") (name "unconnected-(U1-PadPC1)") (class "Default")
      (node (ref "U1") (pin "PC1") (pinfunction "PC1_PC1") (pintype "bidirectional"))
    )
    (net (code "75") (name "unconnected-(U1-PadPC2)") (class "Default")
      (node (ref "U1") (pin "PC2") (pinfunction "PC2_PC2") (pintype "bidirectional"))
    )
    (net (code "76") (name "unconnected-(U1-PadPC3)") (class "Default")
      (node (ref "U1") (pin "PC3") (pinfunction "PC3_PC3") (pintype "bidirectional"))
    )
    (net (code "77") (name "unconnected-(U1-PadPC4)") (class "Default")
      (node (ref "U1") (pin "PC4") (pinfunction "PC4_PC4") (pintype "bidirectional"))
    )
    (net (code "78") (name "unconnected-(U1-PadPC5)") (class "Default")
      (node (ref "U1") (pin "PC5") (pinfunction "PC5_PC5") (pintype "bidirectional"))
    )
    (net (code "79") (name "unconnected-(U1-PadPC6)") (class "Default")
      (node (ref "U1") (pin "PC6") (pinfunction "PC6_PC6") (pintype "bidirectional"))
    )
    (net (code "80") (name "unconnected-(U1-PadPC7)") (class "Default")
      (node (ref "U1") (pin "PC7") (pinfunction "PC7_PC7") (pintype "bidirectional"))
    )
    (net (code "81") (name "unconnected-(U1-PadPC8)") (class "Default")
      (node (ref "U1") (pin "PC8") (pinfunction "PC8_PC8") (pintype "bidirectional"))
    )
    (net (code "82") (name "unconnected-(U1-PadPC9)") (class "Default")
      (node (ref "U1") (pin "PC9") (pinfunction "PC9_PC9") (pintype "bidirectional"))
    )
    (net (code "83") (name "unconnected-(U1-PadPC10)") (class "Default")
      (node (ref "U1") (pin "PC10") (pinfunction "PC10_PC10") (pintype "bidirectional"))
    )
    (net (code "84") (name "unconnected-(U1-PadPC11)") (class "Default")
      (node (ref "U1") (pin "PC11") (pinfunction "PC11_PC11") (pintype "bidirectional"))
    )
    (net (code "85") (name "unconnected-(U1-PadPC12)") (class "Default")
      (node (ref "U1") (pin "PC12") (pinfunction "PC12_PC12") (pintype "bidirectional"))
    )
    (net (code "86") (name "unconnected-(U1-PadPC13)") (class "Default")
      (node (ref "U1") (pin "PC13") (pinfunction "PC13_PC13") (pintype "bidirectional"))
    )
    (net (code "87") (name "unconnected-(U1-PadPC14)") (class "Default")
      (node (ref "U1") (pin "PC14") (pinfunction "PC14_PC14") (pintype "bidirectional"))
    )
    (net (code "88") (name "unconnected-(U1-PadPC15)") (class "Default")
      (node (ref "U1") (pin "PC15") (pinfunction "PC15_PC15") (pintype "bidirectional"))
    )
    (net (code "89") (name "unconnected-(U1-PadPD0)") (class "Default")
      (node (ref "U1") (pin "PD0") (pinfunction "PD0_PD0") (pintype "bidirectional"))
    )
    (net (code "90") (name "unconnected-(U1-PadPD1)") (class "Default")
      (node (ref "U1") (pin "PD1") (pinfunction "PD1_PD1") (pintype "bidirectional"))
    )
    (net (code "91") (name "unconnected-(U1-PadPD2)") (class "Default")
      (node (ref "U1") (pin "PD2") (pinfunction "PD2_PD2") (pintype "bidirectional"))
    )
    (net (code "92") (name "unconnected-(U1-PadPD3)") (class "Default")
      (node (ref "U1") (pin "PD3") (pinfunction "PD3_PD3") (pintype "bidirectional"))
    )
    (net (code "93") (name "unconnected-(U1-PadPD4)") (class "Default")
      (node (ref "U1") (pin "PD4") (pinfunction "PD4_PD4") (pintype "bidirectional"))
    )
    (net (code "94") (name "unconnected-(U1-PadPD5)") (class "Default")
      (node (ref "U1") (pin "PD5") (pinfunction "PD5_PD5") (pintype "bidirectional"))
    )
    (net (code "95") (name "unconnected-(U1-PadPD6)") (class "Default")
      (node (ref "U1") (pin "PD6") (pinfunction "PD6_PD6") (pintype "bidirectional"))
    )
    (net (code "96") (name "unconnected-(U1-PadPD7)") (class "Default")
      (node (ref "U1") (pin "PD7") (pinfunction "PD7_PD7") (pintype "bidirectional"))
    )
    (net (code "97") (name "unconnected-(U1-PadPD8)") (class "Default")
      (node (ref "U1") (pin "PD8") (pinfunction "PD8_PD8") (pintype "bidirectional"))
    )
    (net (code "98") (name "unconnected-(U1-PadPD9)") (class "Default")
      (node (ref "U1") (pin "PD9") (pinfunction "PD9_PD9") (pintype "bidirectional"))
    )
    (net (code "99") (name "unconnected-(U1-PadPD10)") (class "Default")
      (node (ref "U1") (pin "PD10") (pinfunction "PD10_PD10") (pintype "bidirectional"))
    )
    (net (code "100") (name "unconnected-(U1-PadPE0)") (class "Default")
      (node (ref "U1") (pin "PE0") (pinfunction "PE0_PE0") (pintype "bidirectional"))
    )
    (net (code "101") (name "unconnected-(U1-PadPE1)") (class "Default")
      (node (ref "U1") (pin "PE1") (pinfunction "PE1_PE1") (pintype "bidirectional"))
    )
    (net (code "102") (name "unconnected-(U1-PadPE2)") (class "Default")
      (node (ref "U1") (pin "PE2") (pinfunction "PE2_PE2") (pintype "bidirectional"))
    )
    (net (code "103") (name "unconnected-(U1-PadPE3)") (class "Default")
      (node (ref "U1") (pin "PE3") (pinfunction "PE3_PE3") (pintype "bidirectional"))
    )
    (net (code "104") (name "unconnected-(U1-PadPE4)") (class "Default")
      (node (ref "U1") (pin "PE4") (pinfunction "PE4_PE4") (pintype "bidirectional"))
    )
    (net (code "105") (name "unconnected-(U1-PadPE5)") (class "Default")
      (node (ref "U1") (pin "PE5") (pinfunction "PE5_PE5") (pintype "bidirectional"))
    )
    (net (code "106") (name "unconnected-(U1-PadPE6)") (class "Default")
      (node (ref "U1") (pin "PE6") (pinfunction "PE6_PE6") (pintype "bidirectional"))
    )
    (net (code "107") (name "unconnected-(U1-PadPE7)") (class "Default")
      (node (ref "U1") (pin "PE7") (pinfunction "PE7_PE7") (pintype "bidirectional"))
    )
    (net (code "108") (name "unconnected-(U1-PadPE8)") (class "Default")
      (node (ref "U1") (pin "PE8") (pinfunction "PE8_PE8") (pintype "bidirectional"))
    )
    (net (code "109") (name "unconnected-(U1-PadPE10)") (class "Default")
      (node (ref "U1") (pin "PE10") (pinfunction "PE10_PE10") (pintype "bidirectional"))
    )
    (net (code "110") (name "unconnected-(U1-PadPE12)") (class "Default")
      (node (ref "U1") (pin "PE12") (pinfunction "PE12_PE12") (pintype "bidirectional"))
    )
    (net (code "111") (name "unconnected-(U1-PadPE15)") (class "Default")
      (node (ref "U1") (pin "PE15") (pinfunction "PE15_PE15") (pintype "bidirectional"))
    )
  )
)
